# HR911105A.net
KiCad netlist of a schematic drawn in Altium Designer
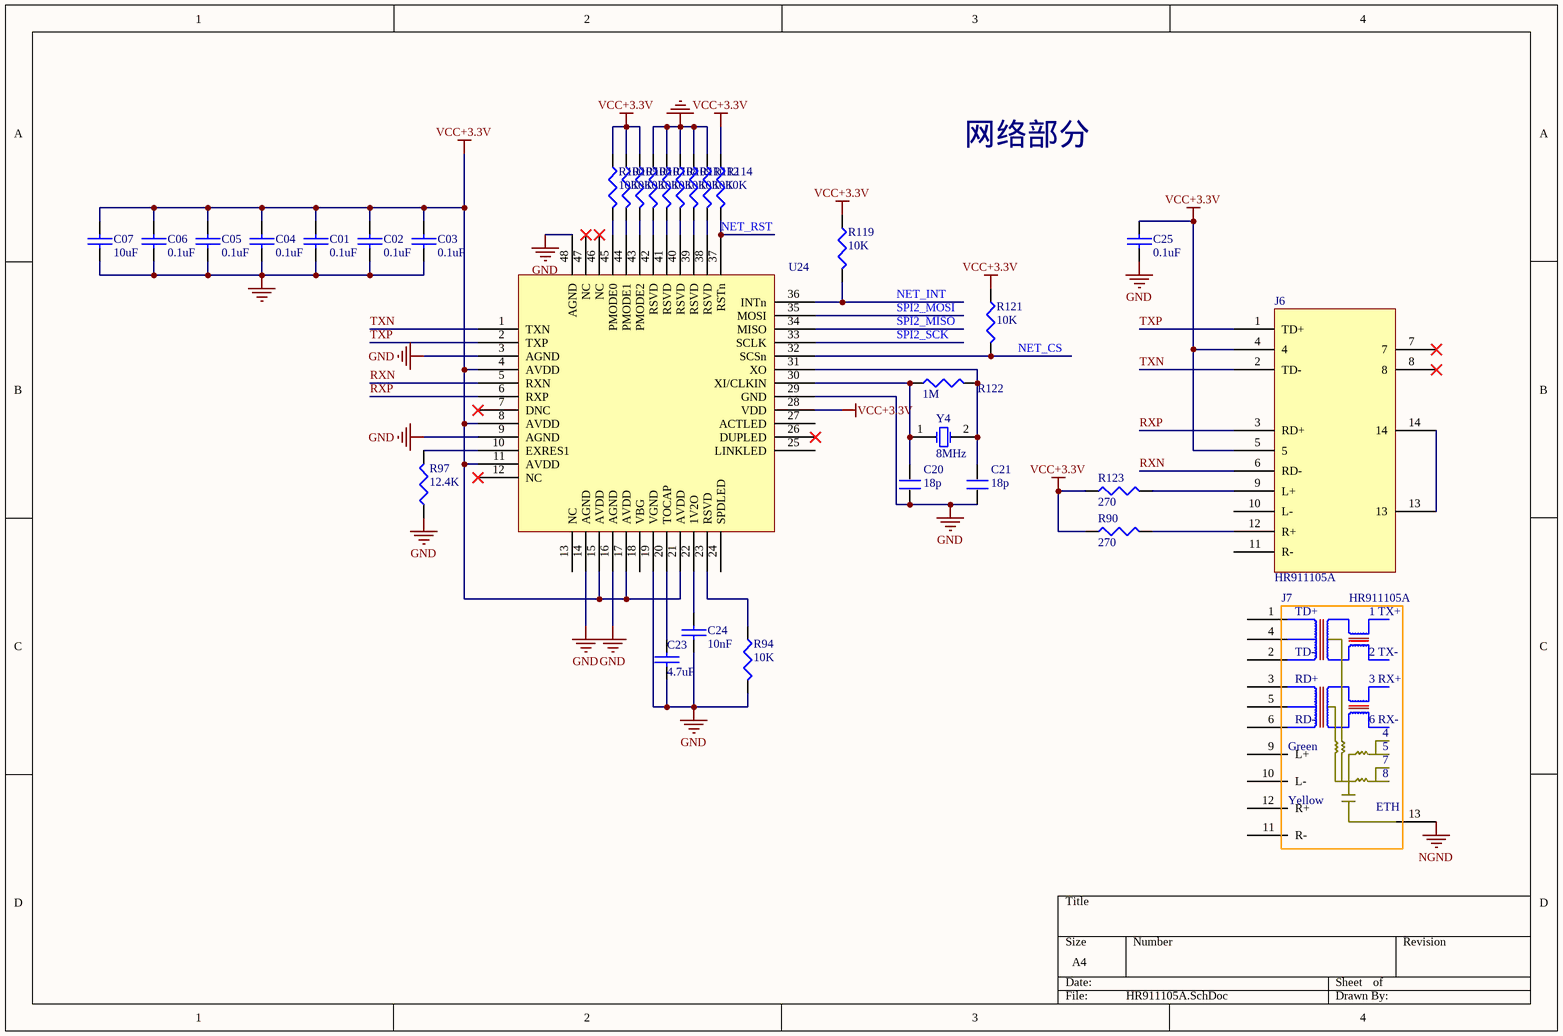
[diagram p0: HR911105A.SchDoc]

(export (version "E")
  (design (tool "Eeschema 10.0.6"))
  (components
    (comp (ref "C01") (value "0.1uF") (footprint "0603") (libsource (lib "INSPUR_SCH") (part "CAP")))
    (comp (ref "C02") (value "0.1uF") (footprint "0603") (libsource (lib "INSPUR_SCH") (part "CAP")))
    (comp (ref "C03") (value "0.1uF") (footprint "0603") (libsource (lib "INSPUR_SCH") (part "CAP")))
    (comp (ref "C04") (value "0.1uF") (footprint "0603") (libsource (lib "INSPUR_SCH") (part "CAP")))
    (comp (ref "C05") (value "0.1uF") (footprint "0603") (libsource (lib "INSPUR_SCH") (part "CAP")))
    (comp (ref "C06") (value "0.1uF") (footprint "0603") (libsource (lib "INSPUR_SCH") (part "CAP")))
    (comp (ref "C07")
      (value "10uF")
      (footprint "0805")
      (description "0.1uF")
      (libsource (lib "INSPUR_SCH") (part "CAP"))
    )
    (comp (ref "C20") (value "18p") (footprint "0603") (libsource (lib "mylib") (part "C")))
    (comp (ref "C21") (value "18p") (footprint "0603") (libsource (lib "mylib") (part "C")))
    (comp (ref "C23")
      (value "4.7uF")
      (footprint "0603")
      (description "0.1uF")
      (libsource (lib "INSPUR_SCH") (part "CAP"))
    )
    (comp (ref "C24") (value "10nF") (footprint "0603") (libsource (lib "INSPUR_SCH") (part "CAP")))
    (comp (ref "C25") (value "0.1uF") (footprint "0603") (libsource (lib "INSPUR_SCH") (part "CAP")))
    (comp (ref "J6")
      (value "HR911105A")
      (footprint "HR911105A")
      (libsource (lib "INSPUR_SCH") (part "HR911105A"))
    )
    (comp (ref "J7") (value "HR911105A") (footprint "HR911102") (libsource (lib "*") (part "HR911102")))
    (comp (ref "R90") (value "270") (footprint "0603") (libsource (lib "INSPUR_SCH") (part "RES1")))
    (comp (ref "R94") (value "10K") (footprint "0603") (libsource (lib "INSPUR_SCH") (part "RES1")))
    (comp (ref "R97") (value "12.4K") (footprint "0603") (libsource (lib "INSPUR_SCH") (part "RES1")))
    (comp (ref "R100") (value "10K") (footprint "0603") (libsource (lib "INSPUR_SCH") (part "RES1")))
    (comp (ref "R105") (value "10K") (footprint "0603") (libsource (lib "INSPUR_SCH") (part "RES1")))
    (comp (ref "R106") (value "10K") (footprint "0603") (libsource (lib "INSPUR_SCH") (part "RES1")))
    (comp (ref "R107") (value "10K") (footprint "0603") (libsource (lib "INSPUR_SCH") (part "RES1")))
    (comp (ref "R108") (value "10K") (footprint "0603") (libsource (lib "INSPUR_SCH") (part "RES1")))
    (comp (ref "R109") (value "10K") (footprint "0603") (libsource (lib "INSPUR_SCH") (part "RES1")))
    (comp (ref "R110") (value "10K") (footprint "0603") (libsource (lib "INSPUR_SCH") (part "RES1")))
    (comp (ref "R112") (value "10K") (footprint "0603") (libsource (lib "INSPUR_SCH") (part "RES1")))
    (comp (ref "R114") (value "10K") (footprint "0603") (libsource (lib "INSPUR_SCH") (part "RES1")))
    (comp (ref "R119") (value "10K") (footprint "0603") (libsource (lib "INSPUR_SCH") (part "RES1")))
    (comp (ref "R121") (value "10K") (footprint "0603") (libsource (lib "INSPUR_SCH") (part "RES1")))
    (comp (ref "R122") (value "1M") (footprint "0603") (libsource (lib "INSPUR_SCH") (part "RES1")))
    (comp (ref "R123") (value "270") (footprint "0603") (libsource (lib "INSPUR_SCH") (part "RES1")))
    (comp (ref "U24")
      (value "W5500")
      (footprint "LQFP48_N")
      (description "以太网")
      (libsource (lib "mylib") (part "W5500"))
    )
    (comp (ref "Y4")
      (value "8MHz")
      (footprint "XTAL_US")
      (description "Crystal Oscillator")
      (fields (field (name "PUBLISHER") "Altium Limited"))
      (libsource (lib "mylib") (part "XTAL"))
    )
  )
  (nets
    (net (code "1") (name "/NET_CS") (class "Default")
      (node (ref "R121") (pin "2") (pinfunction "2_2") (pintype "passive"))
      (node (ref "U24") (pin "32") (pinfunction "SCSn_32") (pintype "passive"))
    )
    (net (code "2") (name "/NET_INT") (class "Default")
      (node (ref "R119") (pin "2") (pinfunction "2_2") (pintype "passive"))
      (node (ref "U24") (pin "36") (pinfunction "INTn_36") (pintype "passive"))
    )
    (net (code "3") (name "/NET_RST") (class "Default")
      (node (ref "R114") (pin "2") (pinfunction "2_2") (pintype "passive"))
      (node (ref "U24") (pin "37") (pinfunction "RSTn_37") (pintype "passive"))
    )
    (net (code "4") (name "/RXN") (class "Default")
      (node (ref "J6") (pin "6") (pinfunction "RD-_6") (pintype "passive"))
      (node (ref "U24") (pin "5") (pinfunction "RXN_5") (pintype "passive"))
    )
    (net (code "5") (name "/RXP") (class "Default")
      (node (ref "J6") (pin "3") (pinfunction "RD+_3") (pintype "passive"))
      (node (ref "U24") (pin "6") (pinfunction "RXP_6") (pintype "passive"))
    )
    (net (code "6") (name "/SPI2_MISO") (class "Default")
      (node (ref "U24") (pin "34") (pinfunction "MISO_34") (pintype "passive"))
    )
    (net (code "7") (name "/SPI2_MOSI") (class "Default")
      (node (ref "U24") (pin "35") (pinfunction "MOSI_35") (pintype "passive"))
    )
    (net (code "8") (name "/SPI2_SCK") (class "Default")
      (node (ref "U24") (pin "33") (pinfunction "SCLK_33") (pintype "passive"))
    )
    (net (code "9") (name "/TXN") (class "Default")
      (node (ref "J6") (pin "2") (pinfunction "TD-_2") (pintype "passive"))
      (node (ref "U24") (pin "1") (pinfunction "TXN_1") (pintype "passive"))
    )
    (net (code "10") (name "/TXP") (class "Default")
      (node (ref "J6") (pin "1") (pinfunction "TD+_1") (pintype "passive"))
      (node (ref "U24") (pin "2") (pinfunction "TXP_2") (pintype "passive"))
    )
    (net (code "11") (name "GND") (class "Default")
      (node (ref "C01") (pin "2") (pinfunction "2_2") (pintype "passive"))
      (node (ref "C02") (pin "2") (pinfunction "2_2") (pintype "passive"))
      (node (ref "C03") (pin "2") (pinfunction "2_2") (pintype "passive"))
      (node (ref "C04") (pin "2") (pinfunction "2_2") (pintype "passive"))
      (node (ref "C05") (pin "2") (pinfunction "2_2") (pintype "passive"))
      (node (ref "C06") (pin "2") (pinfunction "2_2") (pintype "passive"))
      (node (ref "C07") (pin "1") (pinfunction "1_1") (pintype "passive"))
      (node (ref "C20") (pin "1") (pintype "passive"))
      (node (ref "C21") (pin "1") (pintype "passive"))
      (node (ref "C23") (pin "1") (pinfunction "1_1") (pintype "passive"))
      (node (ref "C24") (pin "2") (pinfunction "2_2") (pintype "passive"))
      (node (ref "C25") (pin "2") (pinfunction "2_2") (pintype "passive"))
      (node (ref "R107") (pin "1") (pinfunction "1_1") (pintype "passive"))
      (node (ref "R108") (pin "1") (pinfunction "1_1") (pintype "passive"))
      (node (ref "R109") (pin "1") (pinfunction "1_1") (pintype "passive"))
      (node (ref "R110") (pin "1") (pinfunction "1_1") (pintype "passive"))
      (node (ref "R112") (pin "1") (pinfunction "1_1") (pintype "passive"))
      (node (ref "R94") (pin "2") (pinfunction "2_2") (pintype "passive"))
      (node (ref "R97") (pin "1") (pinfunction "1_1") (pintype "passive"))
      (node (ref "U24") (pin "14") (pinfunction "AGND_14") (pintype "passive"))
      (node (ref "U24") (pin "16") (pinfunction "AGND_16") (pintype "passive"))
      (node (ref "U24") (pin "19") (pinfunction "VGND_19") (pintype "passive"))
      (node (ref "U24") (pin "29") (pinfunction "GND_29") (pintype "passive"))
      (node (ref "U24") (pin "3") (pinfunction "AGND_3") (pintype "passive"))
      (node (ref "U24") (pin "48") (pinfunction "AGND_48") (pintype "passive"))
      (node (ref "U24") (pin "9") (pinfunction "AGND_9") (pintype "passive"))
    )
    (net (code "12") (name "NGND") (class "Default") (node (ref "J7") (pin "13") (pintype "passive")))
    (net (code "13") (name "Net-(J6-L+)") (class "Default")
      (node (ref "J6") (pin "9") (pinfunction "L+_9") (pintype "passive"))
      (node (ref "R123") (pin "2") (pinfunction "2_2") (pintype "passive"))
    )
    (net (code "14") (name "Net-(J6-Pad13)") (class "Default")
      (node (ref "J6") (pin "13") (pinfunction "13_13") (pintype "passive"))
      (node (ref "J6") (pin "14") (pinfunction "14_14") (pintype "passive"))
    )
    (net (code "15") (name "Net-(J6-R+)") (class "Default")
      (node (ref "J6") (pin "12") (pinfunction "R+_12") (pintype "passive"))
      (node (ref "R90") (pin "2") (pinfunction "2_2") (pintype "passive"))
    )
    (net (code "16") (name "Net-(R94-Pad1)") (class "Default")
      (node (ref "R94") (pin "1") (pinfunction "1_1") (pintype "passive"))
      (node (ref "U24") (pin "23") (pinfunction "RSVD_23") (pintype "passive"))
    )
    (net (code "17") (name "Net-(R107-Pad2)") (class "Default")
      (node (ref "R107") (pin "2") (pinfunction "2_2") (pintype "passive"))
      (node (ref "U24") (pin "42") (pinfunction "RSVD_42") (pintype "passive"))
    )
    (net (code "18") (name "Net-(R108-Pad2)") (class "Default")
      (node (ref "R108") (pin "2") (pinfunction "2_2") (pintype "passive"))
      (node (ref "U24") (pin "41") (pinfunction "RSVD_41") (pintype "passive"))
    )
    (net (code "19") (name "Net-(R109-Pad2)") (class "Default")
      (node (ref "R109") (pin "2") (pinfunction "2_2") (pintype "passive"))
      (node (ref "U24") (pin "40") (pinfunction "RSVD_40") (pintype "passive"))
    )
    (net (code "20") (name "Net-(R110-Pad2)") (class "Default")
      (node (ref "R110") (pin "2") (pinfunction "2_2") (pintype "passive"))
      (node (ref "U24") (pin "39") (pinfunction "RSVD_39") (pintype "passive"))
    )
    (net (code "21") (name "Net-(R112-Pad2)") (class "Default")
      (node (ref "R112") (pin "2") (pinfunction "2_2") (pintype "passive"))
      (node (ref "U24") (pin "38") (pinfunction "RSVD_38") (pintype "passive"))
    )
    (net (code "22") (name "Net-(U24-1V2O)") (class "Default")
      (node (ref "C24") (pin "1") (pinfunction "1_1") (pintype "passive"))
      (node (ref "U24") (pin "22") (pinfunction "1V2O_22") (pintype "passive"))
    )
    (net (code "23") (name "Net-(U24-EXRES1)") (class "Default")
      (node (ref "R97") (pin "2") (pinfunction "2_2") (pintype "passive"))
      (node (ref "U24") (pin "10") (pinfunction "EXRES1_10") (pintype "passive"))
    )
    (net (code "24") (name "Net-(U24-PMODE0)") (class "Default")
      (node (ref "R100") (pin "2") (pinfunction "2_2") (pintype "passive"))
      (node (ref "U24") (pin "45") (pinfunction "PMODE0_45") (pintype "passive"))
    )
    (net (code "25") (name "Net-(U24-PMODE1)") (class "Default")
      (node (ref "R105") (pin "2") (pinfunction "2_2") (pintype "passive"))
      (node (ref "U24") (pin "44") (pinfunction "PMODE1_44") (pintype "passive"))
    )
    (net (code "26") (name "Net-(U24-PMODE2)") (class "Default")
      (node (ref "R106") (pin "2") (pinfunction "2_2") (pintype "passive"))
      (node (ref "U24") (pin "43") (pinfunction "PMODE2_43") (pintype "passive"))
    )
    (net (code "27") (name "Net-(U24-TOCAP)") (class "Default")
      (node (ref "C23") (pin "2") (pinfunction "2_2") (pintype "passive"))
      (node (ref "U24") (pin "20") (pinfunction "TOCAP_20") (pintype "passive"))
    )
    (net (code "28") (name "Net-(U24-XI{slash}CLKIN)") (class "Default")
      (node (ref "C20") (pin "2") (pintype "passive"))
      (node (ref "R122") (pin "1") (pinfunction "1_1") (pintype "passive"))
      (node (ref "U24") (pin "30") (pinfunction "XI/CLKIN_30") (pintype "passive"))
      (node (ref "Y4") (pin "1") (pinfunction "OSC1_1") (pintype "passive"))
    )
    (net (code "29") (name "Net-(U24-XO)") (class "Default")
      (node (ref "C21") (pin "2") (pintype "passive"))
      (node (ref "R122") (pin "2") (pinfunction "2_2") (pintype "passive"))
      (node (ref "U24") (pin "31") (pinfunction "XO_31") (pintype "passive"))
      (node (ref "Y4") (pin "2") (pinfunction "OSC2_2") (pintype "passive"))
    )
    (net (code "30") (name "VCC+3.3V") (class "Default")
      (node (ref "C01") (pin "1") (pinfunction "1_1") (pintype "passive"))
      (node (ref "C02") (pin "1") (pinfunction "1_1") (pintype "passive"))
      (node (ref "C03") (pin "1") (pinfunction "1_1") (pintype "passive"))
      (node (ref "C04") (pin "1") (pinfunction "1_1") (pintype "passive"))
      (node (ref "C05") (pin "1") (pinfunction "1_1") (pintype "passive"))
      (node (ref "C06") (pin "1") (pinfunction "1_1") (pintype "passive"))
      (node (ref "C07") (pin "2") (pinfunction "2_2") (pintype "passive"))
      (node (ref "C25") (pin "1") (pinfunction "1_1") (pintype "passive"))
      (node (ref "J6") (pin "4") (pinfunction "4_4") (pintype "passive"))
      (node (ref "J6") (pin "5") (pinfunction "5_5") (pintype "passive"))
      (node (ref "R100") (pin "1") (pinfunction "1_1") (pintype "passive"))
      (node (ref "R105") (pin "1") (pinfunction "1_1") (pintype "passive"))
      (node (ref "R106") (pin "1") (pinfunction "1_1") (pintype "passive"))
      (node (ref "R114") (pin "1") (pinfunction "1_1") (pintype "passive"))
      (node (ref "R119") (pin "1") (pinfunction "1_1") (pintype "passive"))
      (node (ref "R121") (pin "1") (pinfunction "1_1") (pintype "passive"))
      (node (ref "R123") (pin "1") (pinfunction "1_1") (pintype "passive"))
      (node (ref "R90") (pin "1") (pinfunction "1_1") (pintype "passive"))
      (node (ref "U24") (pin "11") (pinfunction "AVDD_11") (pintype "passive"))
      (node (ref "U24") (pin "15") (pinfunction "AVDD_15") (pintype "passive"))
      (node (ref "U24") (pin "17") (pinfunction "AVDD_17") (pintype "passive"))
      (node (ref "U24") (pin "21") (pinfunction "AVDD_21") (pintype "passive"))
      (node (ref "U24") (pin "28") (pinfunction "VDD_28") (pintype "passive"))
      (node (ref "U24") (pin "4") (pinfunction "AVDD_4") (pintype "passive"))
      (node (ref "U24") (pin "8") (pinfunction "AVDD_8") (pintype "passive"))
    )
    (net (code "31") (name "unconnected-(J6-L--Pad10)") (class "Default")
      (node (ref "J6") (pin "10") (pinfunction "L-_10") (pintype "passive"))
    )
    (net (code "32") (name "unconnected-(J6-Pad7)") (class "Default")
      (node (ref "J6") (pin "7") (pinfunction "7_7") (pintype "passive+no_connect"))
    )
    (net (code "33") (name "unconnected-(J6-Pad8)") (class "Default")
      (node (ref "J6") (pin "8") (pinfunction "8_8") (pintype "passive+no_connect"))
    )
    (net (code "34") (name "unconnected-(J6-R--Pad11)") (class "Default")
      (node (ref "J6") (pin "11") (pinfunction "R-_11") (pintype "passive"))
    )
    (net (code "35") (name "unconnected-(J7-L+-Pad9)") (class "Default")
      (node (ref "J7") (pin "9") (pinfunction "L+_9") (pintype "passive"))
    )
    (net (code "36") (name "unconnected-(J7-L--Pad10)") (class "Default")
      (node (ref "J7") (pin "10") (pinfunction "L-_10") (pintype "passive"))
    )
    (net (code "37") (name "unconnected-(J7-Pad1)") (class "Default")
      (node (ref "J7") (pin "1") (pintype "passive"))
    )
    (net (code "38") (name "unconnected-(J7-Pad2)") (class "Default")
      (node (ref "J7") (pin "2") (pintype "passive"))
    )
    (net (code "39") (name "unconnected-(J7-Pad3)") (class "Default")
      (node (ref "J7") (pin "3") (pintype "passive"))
    )
    (net (code "40") (name "unconnected-(J7-Pad4)") (class "Default")
      (node (ref "J7") (pin "4") (pintype "passive"))
    )
    (net (code "41") (name "unconnected-(J7-Pad5)") (class "Default")
      (node (ref "J7") (pin "5") (pintype "passive"))
    )
    (net (code "42") (name "unconnected-(J7-Pad6)") (class "Default")
      (node (ref "J7") (pin "6") (pintype "passive"))
    )
    (net (code "43") (name "unconnected-(J7-R+-Pad12)") (class "Default")
      (node (ref "J7") (pin "12") (pinfunction "R+_12") (pintype "passive"))
    )
    (net (code "44") (name "unconnected-(J7-R--Pad11)") (class "Default")
      (node (ref "J7") (pin "11") (pinfunction "R-_11") (pintype "passive"))
    )
    (net (code "45") (name "unconnected-(U24-ACTLED-Pad27)") (class "Default")
      (node (ref "U24") (pin "27") (pinfunction "ACTLED_27") (pintype "passive"))
    )
    (net (code "46") (name "unconnected-(U24-DNC-Pad7)") (class "Default")
      (node (ref "U24") (pin "7") (pinfunction "DNC_7") (pintype "passive+no_connect"))
    )
    (net (code "47") (name "unconnected-(U24-DUPLED-Pad26)") (class "Default")
      (node (ref "U24") (pin "26") (pinfunction "DUPLED_26") (pintype "passive+no_connect"))
    )
    (net (code "48") (name "unconnected-(U24-LINKLED-Pad25)") (class "Default")
      (node (ref "U24") (pin "25") (pinfunction "LINKLED_25") (pintype "passive"))
    )
    (net (code "49") (name "unconnected-(U24-NC-Pad12)") (class "Default")
      (node (ref "U24") (pin "12") (pinfunction "NC_12") (pintype "passive+no_connect"))
    )
    (net (code "50") (name "unconnected-(U24-NC-Pad13)") (class "Default")
      (node (ref "U24") (pin "13") (pinfunction "NC_13") (pintype "passive"))
    )
    (net (code "51") (name "unconnected-(U24-NC-Pad46)") (class "Default")
      (node (ref "U24") (pin "46") (pinfunction "NC_46") (pintype "passive+no_connect"))
    )
    (net (code "52") (name "unconnected-(U24-NC-Pad47)") (class "Default")
      (node (ref "U24") (pin "47") (pinfunction "NC_47") (pintype "passive+no_connect"))
    )
    (net (code "53") (name "unconnected-(U24-SPDLED-Pad24)") (class "Default")
      (node (ref "U24") (pin "24") (pinfunction "SPDLED_24") (pintype "passive"))
    )
    (net (code "54") (name "unconnected-(U24-VBG-Pad18)") (class "Default")
      (node (ref "U24") (pin "18") (pinfunction "VBG_18") (pintype "passive"))
    )
  )
)
